# C64-usb-loader.net
KiCad netlist of a schematic drawn in EAGLE
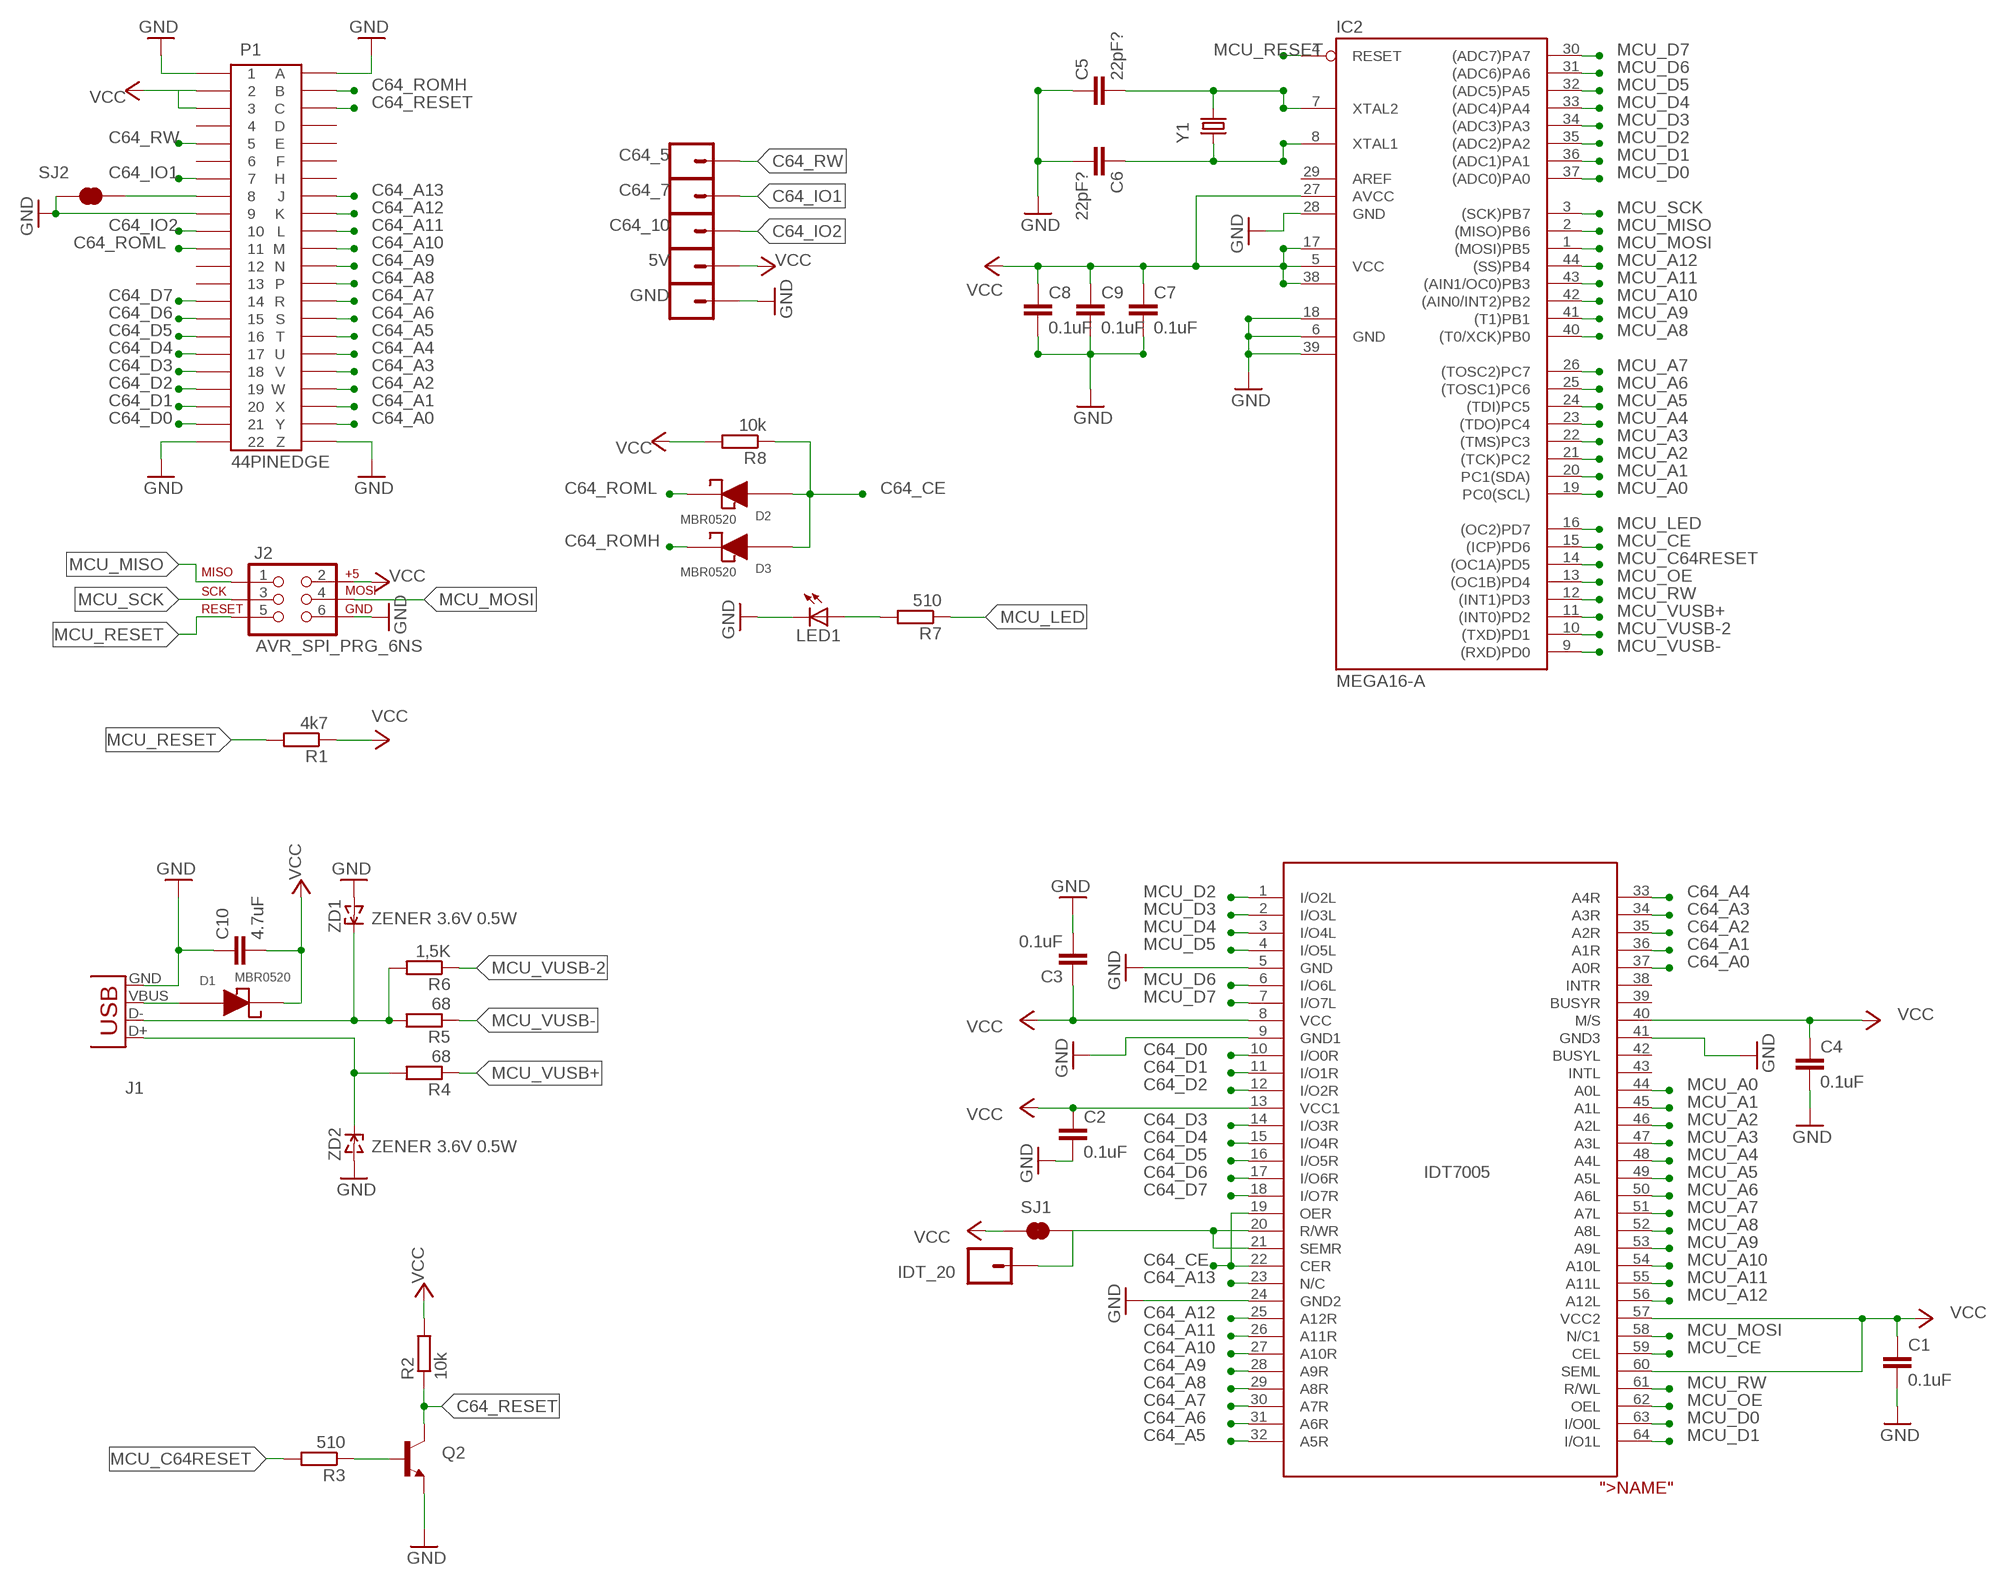
[diagram p0: schematic, sheet 1]

(export (version "E")
  (design (tool "Eeschema 10.0.6"))
  (components
    (comp (ref "5V")
      (value "M01PTH")
      (footprint "eagle-import:1X01")
      (libsource (lib "eagle-import") (part "M01PTH"))
    )
    (comp (ref "C1")
      (value "0.1uF")
      (footprint "eagle-import:C0805")
      (libsource (lib "eagle-import") (part "C-EUC0805"))
    )
    (comp (ref "C2")
      (value "0.1uF")
      (footprint "eagle-import:C0805")
      (libsource (lib "eagle-import") (part "C-EUC0805"))
    )
    (comp (ref "C3")
      (value "0.1uF")
      (footprint "eagle-import:C0805")
      (libsource (lib "eagle-import") (part "C-EUC0805"))
    )
    (comp (ref "C4")
      (value "0.1uF")
      (footprint "eagle-import:C0805")
      (libsource (lib "eagle-import") (part "C-EUC0805"))
    )
    (comp (ref "C5")
      (value "22pF?")
      (footprint "eagle-import:C0805")
      (libsource (lib "eagle-import") (part "C-EUC0805"))
    )
    (comp (ref "C6")
      (value "22pF?")
      (footprint "eagle-import:C0805")
      (libsource (lib "eagle-import") (part "C-EUC0805"))
    )
    (comp (ref "C7")
      (value "0.1uF")
      (footprint "eagle-import:C0805")
      (libsource (lib "eagle-import") (part "C-EUC0805"))
    )
    (comp (ref "C8")
      (value "0.1uF")
      (footprint "eagle-import:C0805")
      (libsource (lib "eagle-import") (part "C-EUC0805"))
    )
    (comp (ref "C9")
      (value "0.1uF")
      (footprint "eagle-import:C0805")
      (libsource (lib "eagle-import") (part "C-EUC0805"))
    )
    (comp (ref "C10")
      (value "4.7uF")
      (footprint "eagle-import:C0805")
      (libsource (lib "eagle-import") (part "C-EUC0805"))
    )
    (comp (ref "C64_5")
      (value "M01PTH")
      (footprint "eagle-import:1X01")
      (libsource (lib "eagle-import") (part "M01PTH"))
    )
    (comp (ref "C64_7")
      (value "M01PTH")
      (footprint "eagle-import:1X01")
      (libsource (lib "eagle-import") (part "M01PTH"))
    )
    (comp (ref "C64_10")
      (value "M01PTH")
      (footprint "eagle-import:1X01")
      (libsource (lib "eagle-import") (part "M01PTH"))
    )
    (comp (ref "D1")
      (value "MBR0520")
      (footprint "eagle-import:SOD-123")
      (libsource (lib "eagle-import") (part "MBR0520"))
    )
    (comp (ref "D2")
      (value "MBR0520")
      (footprint "eagle-import:SOD-123")
      (libsource (lib "eagle-import") (part "MBR0520"))
    )
    (comp (ref "D3")
      (value "MBR0520")
      (footprint "eagle-import:SOD-123")
      (libsource (lib "eagle-import") (part "MBR0520"))
    )
    (comp (ref "GND")
      (value "M01PTH")
      (footprint "eagle-import:1X01")
      (libsource (lib "eagle-import") (part "M01PTH"))
    )
    (comp (ref "IC1")
      (value "IDT7005")
      (footprint "eagle-import:TQFP64")
      (libsource (lib "eagle-import") (part "IDT7005"))
    )
    (comp (ref "IC2")
      (value "MEGA16-A")
      (footprint "eagle-import:TQFP44")
      (fields (field (name "MPN") "ATMEGA16-16AU"))
      (libsource (lib "eagle-import") (part "MEGA16-A"))
    )
    (comp (ref "IDT_20")
      (value "M01PTH")
      (footprint "eagle-import:1X01")
      (libsource (lib "eagle-import") (part "M01PTH"))
    )
    (comp (ref "J1")
      (value "USB-B")
      (footprint "eagle-import:B")
      (libsource (lib "eagle-import") (part "USB-B"))
    )
    (comp (ref "J2")
      (value "AVR_SPI_PRG_6NS")
      (footprint "eagle-import:2X3-NS")
      (libsource (lib "eagle-import") (part "AVR_SPI_PRG_6NS"))
    )
    (comp (ref "LED1")
      (value "LED1206")
      (footprint "eagle-import:LED-1206")
      (libsource (lib "eagle-import") (part "LED1206"))
    )
    (comp (ref "P1")
      (value "44PINEDGE")
      (footprint "eagle-import:44PINEDGE")
      (libsource (lib "eagle-import") (part "44PINEDGE"))
    )
    (comp (ref "Q2")
      (value "TRANSISTOR_NPNSOT23-3")
      (footprint "eagle-import:SOT23-3")
      (libsource (lib "eagle-import") (part "TRANSISTOR_NPNSOT23-3"))
    )
    (comp (ref "R1")
      (value "4k7")
      (footprint "eagle-import:M0805")
      (libsource (lib "eagle-import") (part "R-EU_M0805"))
    )
    (comp (ref "R2")
      (value "10k")
      (footprint "eagle-import:M0805")
      (libsource (lib "eagle-import") (part "R-EU_M0805"))
    )
    (comp (ref "R3")
      (value "510")
      (footprint "eagle-import:M0805")
      (libsource (lib "eagle-import") (part "R-EU_M0805"))
    )
    (comp (ref "R4")
      (value "68")
      (footprint "eagle-import:M0805")
      (libsource (lib "eagle-import") (part "R-EU_M0805"))
    )
    (comp (ref "R5")
      (value "68")
      (footprint "eagle-import:M0805")
      (libsource (lib "eagle-import") (part "R-EU_M0805"))
    )
    (comp (ref "R6")
      (value "1,5K")
      (footprint "eagle-import:M0805")
      (libsource (lib "eagle-import") (part "R-EU_M0805"))
    )
    (comp (ref "R7")
      (value "510")
      (footprint "eagle-import:M0805")
      (libsource (lib "eagle-import") (part "R-EU_M0805"))
    )
    (comp (ref "R8")
      (value "10k")
      (footprint "eagle-import:M0805")
      (libsource (lib "eagle-import") (part "R-EU_M0805"))
    )
    (comp (ref "SJ1")
      (value "JUMPER-PAD-2-NC_BY_TRACE")
      (footprint "eagle-import:PAD-JUMPER-2-NC_BY_TRACE_YES_SILK")
      (libsource (lib "eagle-import") (part "JUMPER-PAD-2-NC_BY_TRACE"))
    )
    (comp (ref "SJ2")
      (value "JUMPER-PAD-2-NC_BY_TRACE")
      (footprint "eagle-import:PAD-JUMPER-2-NC_BY_TRACE_YES_SILK")
      (libsource (lib "eagle-import") (part "JUMPER-PAD-2-NC_BY_TRACE"))
    )
    (comp (ref "Y1")
      (value "CRYSTALHC49US")
      (footprint "eagle-import:HC49US")
      (libsource (lib "eagle-import") (part "CRYSTALHC49US"))
    )
    (comp (ref "ZD1")
      (value "ZENER 3.6V 0.5W")
      (footprint "eagle-import:SOD-123")
      (libsource (lib "eagle-import") (part "ZENERSOD-123"))
    )
    (comp (ref "ZD2")
      (value "ZENER 3.6V 0.5W")
      (footprint "eagle-import:SOD-123")
      (libsource (lib "eagle-import") (part "ZENERSOD-123"))
    )
  )
  (nets
    (net (code "1") (name "/C64_A0") (class "Default")
      (node (ref "IC1") (pin "37") (pinfunction "A0R_37") (pintype "bidirectional"))
      (node (ref "P1") (pin "Y") (pinfunction "Y_Y") (pintype "passive"))
    )
    (net (code "2") (name "/C64_A1") (class "Default")
      (node (ref "IC1") (pin "36") (pinfunction "A1R_36") (pintype "bidirectional"))
      (node (ref "P1") (pin "X") (pinfunction "X_X") (pintype "passive"))
    )
    (net (code "3") (name "/C64_A2") (class "Default")
      (node (ref "IC1") (pin "35") (pinfunction "A2R_35") (pintype "bidirectional"))
      (node (ref "P1") (pin "W") (pinfunction "W_W") (pintype "passive"))
    )
    (net (code "4") (name "/C64_A3") (class "Default")
      (node (ref "IC1") (pin "34") (pinfunction "A3R_34") (pintype "bidirectional"))
      (node (ref "P1") (pin "V") (pinfunction "V_V") (pintype "passive"))
    )
    (net (code "5") (name "/C64_A4") (class "Default")
      (node (ref "IC1") (pin "33") (pinfunction "A4R_33") (pintype "bidirectional"))
      (node (ref "P1") (pin "U") (pinfunction "U_U") (pintype "passive"))
    )
    (net (code "6") (name "/C64_A5") (class "Default")
      (node (ref "IC1") (pin "32") (pinfunction "A5R_32") (pintype "bidirectional"))
      (node (ref "P1") (pin "T") (pinfunction "T_T") (pintype "passive"))
    )
    (net (code "7") (name "/C64_A6") (class "Default")
      (node (ref "IC1") (pin "31") (pinfunction "A6R_31") (pintype "bidirectional"))
      (node (ref "P1") (pin "S") (pinfunction "S_S") (pintype "passive"))
    )
    (net (code "8") (name "/C64_A7") (class "Default")
      (node (ref "IC1") (pin "30") (pinfunction "A7R_30") (pintype "bidirectional"))
      (node (ref "P1") (pin "R") (pinfunction "R_R") (pintype "passive"))
    )
    (net (code "9") (name "/C64_A8") (class "Default")
      (node (ref "IC1") (pin "29") (pinfunction "A8R_29") (pintype "bidirectional"))
      (node (ref "P1") (pin "P") (pinfunction "P_P") (pintype "passive"))
    )
    (net (code "10") (name "/C64_A9") (class "Default")
      (node (ref "IC1") (pin "28") (pinfunction "A9R_28") (pintype "bidirectional"))
      (node (ref "P1") (pin "N") (pinfunction "N_N") (pintype "passive"))
    )
    (net (code "11") (name "/C64_A10") (class "Default")
      (node (ref "IC1") (pin "27") (pinfunction "A10R_27") (pintype "bidirectional"))
      (node (ref "P1") (pin "M") (pinfunction "M_M") (pintype "passive"))
    )
    (net (code "12") (name "/C64_A11") (class "Default")
      (node (ref "IC1") (pin "26") (pinfunction "A11R_26") (pintype "bidirectional"))
      (node (ref "P1") (pin "L") (pinfunction "L_L") (pintype "passive"))
    )
    (net (code "13") (name "/C64_A12") (class "Default")
      (node (ref "IC1") (pin "25") (pinfunction "A12R_25") (pintype "bidirectional"))
      (node (ref "P1") (pin "K") (pinfunction "K_K") (pintype "passive"))
    )
    (net (code "14") (name "/C64_A13") (class "Default")
      (node (ref "IC1") (pin "23") (pinfunction "N/C_23") (pintype "bidirectional"))
      (node (ref "P1") (pin "J") (pinfunction "J_J") (pintype "passive"))
    )
    (net (code "15") (name "/C64_CE") (class "Default")
      (node (ref "D2") (pin "2") (pinfunction "AN_2") (pintype "passive"))
      (node (ref "D3") (pin "2") (pinfunction "AN_2") (pintype "passive"))
      (node (ref "IC1") (pin "19") (pinfunction "OER_19") (pintype "bidirectional"))
      (node (ref "IC1") (pin "22") (pinfunction "CER_22") (pintype "bidirectional"))
      (node (ref "R8") (pin "1") (pinfunction "1_1") (pintype "passive"))
    )
    (net (code "16") (name "/C64_D0") (class "Default")
      (node (ref "IC1") (pin "10") (pinfunction "I/O0R_10") (pintype "bidirectional"))
      (node (ref "P1") (pin "21") (pinfunction "21_21") (pintype "passive"))
    )
    (net (code "17") (name "/C64_D1") (class "Default")
      (node (ref "IC1") (pin "11") (pinfunction "I/O1R_11") (pintype "bidirectional"))
      (node (ref "P1") (pin "20") (pinfunction "20_20") (pintype "passive"))
    )
    (net (code "18") (name "/C64_D2") (class "Default")
      (node (ref "IC1") (pin "12") (pinfunction "I/O2R_12") (pintype "bidirectional"))
      (node (ref "P1") (pin "19") (pinfunction "19_19") (pintype "passive"))
    )
    (net (code "19") (name "/C64_D3") (class "Default")
      (node (ref "IC1") (pin "14") (pinfunction "I/O3R_14") (pintype "bidirectional"))
      (node (ref "P1") (pin "18") (pinfunction "18_18") (pintype "passive"))
    )
    (net (code "20") (name "/C64_D4") (class "Default")
      (node (ref "IC1") (pin "15") (pinfunction "I/O4R_15") (pintype "bidirectional"))
      (node (ref "P1") (pin "17") (pinfunction "17_17") (pintype "passive"))
    )
    (net (code "21") (name "/C64_D5") (class "Default")
      (node (ref "IC1") (pin "16") (pinfunction "I/O5R_16") (pintype "bidirectional"))
      (node (ref "P1") (pin "16") (pinfunction "16_16") (pintype "passive"))
    )
    (net (code "22") (name "/C64_D6") (class "Default")
      (node (ref "IC1") (pin "17") (pinfunction "I/O6R_17") (pintype "bidirectional"))
      (node (ref "P1") (pin "15") (pinfunction "15_15") (pintype "passive"))
    )
    (net (code "23") (name "/C64_D7") (class "Default")
      (node (ref "IC1") (pin "18") (pinfunction "I/O7R_18") (pintype "bidirectional"))
      (node (ref "P1") (pin "14") (pinfunction "14_14") (pintype "passive"))
    )
    (net (code "24") (name "/C64_ROMH") (class "Default")
      (node (ref "D3") (pin "1") (pinfunction "CA_1") (pintype "passive"))
      (node (ref "P1") (pin "B") (pinfunction "B_B") (pintype "passive"))
    )
    (net (code "25") (name "/C64_ROML") (class "Default")
      (node (ref "D2") (pin "1") (pinfunction "CA_1") (pintype "passive"))
      (node (ref "P1") (pin "11") (pinfunction "11_11") (pintype "passive"))
    )
    (net (code "26") (name "/MCU_A0") (class "Default")
      (node (ref "IC1") (pin "44") (pinfunction "A0L_44") (pintype "bidirectional"))
      (node (ref "IC2") (pin "19") (pinfunction "PC0(SCL)_19") (pintype "bidirectional"))
    )
    (net (code "27") (name "/MCU_A1") (class "Default")
      (node (ref "IC1") (pin "45") (pinfunction "A1L_45") (pintype "bidirectional"))
      (node (ref "IC2") (pin "20") (pinfunction "PC1(SDA)_20") (pintype "bidirectional"))
    )
    (net (code "28") (name "/MCU_A2") (class "Default")
      (node (ref "IC1") (pin "46") (pinfunction "A2L_46") (pintype "bidirectional"))
      (node (ref "IC2") (pin "21") (pinfunction "(TCK)PC2_21") (pintype "bidirectional"))
    )
    (net (code "29") (name "/MCU_A3") (class "Default")
      (node (ref "IC1") (pin "47") (pinfunction "A3L_47") (pintype "bidirectional"))
      (node (ref "IC2") (pin "22") (pinfunction "(TMS)PC3_22") (pintype "bidirectional"))
    )
    (net (code "30") (name "/MCU_A4") (class "Default")
      (node (ref "IC1") (pin "48") (pinfunction "A4L_48") (pintype "bidirectional"))
      (node (ref "IC2") (pin "23") (pinfunction "(TDO)PC4_23") (pintype "bidirectional"))
    )
    (net (code "31") (name "/MCU_A5") (class "Default")
      (node (ref "IC1") (pin "49") (pinfunction "A5L_49") (pintype "bidirectional"))
      (node (ref "IC2") (pin "24") (pinfunction "(TDI)PC5_24") (pintype "bidirectional"))
    )
    (net (code "32") (name "/MCU_A6") (class "Default")
      (node (ref "IC1") (pin "50") (pinfunction "A6L_50") (pintype "bidirectional"))
      (node (ref "IC2") (pin "25") (pinfunction "(TOSC1)PC6_25") (pintype "bidirectional"))
    )
    (net (code "33") (name "/MCU_A7") (class "Default")
      (node (ref "IC1") (pin "51") (pinfunction "A7L_51") (pintype "bidirectional"))
      (node (ref "IC2") (pin "26") (pinfunction "(TOSC2)PC7_26") (pintype "bidirectional"))
    )
    (net (code "34") (name "/MCU_A8") (class "Default")
      (node (ref "IC1") (pin "52") (pinfunction "A8L_52") (pintype "bidirectional"))
      (node (ref "IC2") (pin "40") (pinfunction "(T0/XCK)PB0_40") (pintype "bidirectional"))
    )
    (net (code "35") (name "/MCU_A9") (class "Default")
      (node (ref "IC1") (pin "53") (pinfunction "A9L_53") (pintype "bidirectional"))
      (node (ref "IC2") (pin "41") (pinfunction "(T1)PB1_41") (pintype "bidirectional"))
    )
    (net (code "36") (name "/MCU_A10") (class "Default")
      (node (ref "IC1") (pin "54") (pinfunction "A10L_54") (pintype "bidirectional"))
      (node (ref "IC2") (pin "42") (pinfunction "(AIN0/INT2)PB2_42") (pintype "bidirectional"))
    )
    (net (code "37") (name "/MCU_A11") (class "Default")
      (node (ref "IC1") (pin "55") (pinfunction "A11L_55") (pintype "bidirectional"))
      (node (ref "IC2") (pin "43") (pinfunction "(AIN1/OC0)PB3_43") (pintype "bidirectional"))
    )
    (net (code "38") (name "/MCU_A12") (class "Default")
      (node (ref "IC1") (pin "56") (pinfunction "A12L_56") (pintype "bidirectional"))
      (node (ref "IC2") (pin "44") (pinfunction "(SS)PB4_44") (pintype "bidirectional"))
    )
    (net (code "39") (name "/MCU_CE") (class "Default")
      (node (ref "IC1") (pin "59") (pinfunction "CEL_59") (pintype "bidirectional"))
      (node (ref "IC2") (pin "15") (pinfunction "(ICP)PD6_15") (pintype "bidirectional"))
    )
    (net (code "40") (name "/MCU_D0") (class "Default")
      (node (ref "IC1") (pin "63") (pinfunction "I/O0L_63") (pintype "bidirectional"))
      (node (ref "IC2") (pin "37") (pinfunction "(ADC0)PA0_37") (pintype "bidirectional"))
    )
    (net (code "41") (name "/MCU_D1") (class "Default")
      (node (ref "IC1") (pin "64") (pinfunction "I/O1L_64") (pintype "bidirectional"))
      (node (ref "IC2") (pin "36") (pinfunction "(ADC1)PA1_36") (pintype "bidirectional"))
    )
    (net (code "42") (name "/MCU_D2") (class "Default")
      (node (ref "IC1") (pin "1") (pinfunction "I/O2L_1") (pintype "bidirectional"))
      (node (ref "IC2") (pin "35") (pinfunction "(ADC2)PA2_35") (pintype "bidirectional"))
    )
    (net (code "43") (name "/MCU_D3") (class "Default")
      (node (ref "IC1") (pin "2") (pinfunction "I/O3L_2") (pintype "bidirectional"))
      (node (ref "IC2") (pin "34") (pinfunction "(ADC3)PA3_34") (pintype "bidirectional"))
    )
    (net (code "44") (name "/MCU_D4") (class "Default")
      (node (ref "IC1") (pin "3") (pinfunction "I/O4L_3") (pintype "bidirectional"))
      (node (ref "IC2") (pin "33") (pinfunction "(ADC4)PA4_33") (pintype "bidirectional"))
    )
    (net (code "45") (name "/MCU_D5") (class "Default")
      (node (ref "IC1") (pin "4") (pinfunction "I/O5L_4") (pintype "bidirectional"))
      (node (ref "IC2") (pin "32") (pinfunction "(ADC5)PA5_32") (pintype "bidirectional"))
    )
    (net (code "46") (name "/MCU_D6") (class "Default")
      (node (ref "IC1") (pin "6") (pinfunction "I/O6L_6") (pintype "bidirectional"))
      (node (ref "IC2") (pin "31") (pinfunction "(ADC6)PA6_31") (pintype "bidirectional"))
    )
    (net (code "47") (name "/MCU_D7") (class "Default")
      (node (ref "IC1") (pin "7") (pinfunction "I/O7L_7") (pintype "bidirectional"))
      (node (ref "IC2") (pin "30") (pinfunction "(ADC7)PA7_30") (pintype "bidirectional"))
    )
    (net (code "48") (name "/MCU_OE") (class "Default")
      (node (ref "IC1") (pin "62") (pinfunction "OEL_62") (pintype "bidirectional"))
      (node (ref "IC2") (pin "13") (pinfunction "(OC1B)PD4_13") (pintype "bidirectional"))
    )
    (net (code "49") (name "/MCU_RW") (class "Default")
      (node (ref "IC1") (pin "61") (pinfunction "R/WL_61") (pintype "bidirectional"))
      (node (ref "IC2") (pin "12") (pinfunction "(INT1)PD3_12") (pintype "bidirectional"))
    )
    (net (code "50") (name "C64_IO1") (class "Default")
      (node (ref "C64_7") (pin "1") (pinfunction "1_1") (pintype "passive"))
      (node (ref "P1") (pin "7") (pinfunction "7_7") (pintype "passive"))
    )
    (net (code "51") (name "C64_IO2") (class "Default")
      (node (ref "C64_10") (pin "1") (pinfunction "1_1") (pintype "passive"))
      (node (ref "P1") (pin "10") (pinfunction "10_10") (pintype "passive"))
    )
    (net (code "52") (name "C64_RESET") (class "Default")
      (node (ref "P1") (pin "C") (pinfunction "C_C") (pintype "passive"))
      (node (ref "Q2") (pin "3") (pinfunction "C_3") (pintype "passive"))
      (node (ref "R2") (pin "1") (pinfunction "1_1") (pintype "passive"))
    )
    (net (code "53") (name "C64_RW") (class "Default")
      (node (ref "C64_5") (pin "1") (pinfunction "1_1") (pintype "passive"))
      (node (ref "P1") (pin "5") (pinfunction "5_5") (pintype "passive"))
    )
    (net (code "54") (name "GND") (class "Default")
      (node (ref "C1") (pin "2") (pinfunction "2_2") (pintype "passive"))
      (node (ref "C10") (pin "1") (pinfunction "1_1") (pintype "passive"))
      (node (ref "C2") (pin "2") (pinfunction "2_2") (pintype "passive"))
      (node (ref "C3") (pin "2") (pinfunction "2_2") (pintype "passive"))
      (node (ref "C4") (pin "2") (pinfunction "2_2") (pintype "passive"))
      (node (ref "C5") (pin "1") (pinfunction "1_1") (pintype "passive"))
      (node (ref "C6") (pin "2") (pinfunction "2_2") (pintype "passive"))
      (node (ref "C7") (pin "2") (pinfunction "2_2") (pintype "passive"))
      (node (ref "C8") (pin "2") (pinfunction "2_2") (pintype "passive"))
      (node (ref "C9") (pin "2") (pinfunction "2_2") (pintype "passive"))
      (node (ref "GND") (pin "1") (pinfunction "1_1") (pintype "passive"))
      (node (ref "IC1") (pin "24") (pinfunction "GND2_24") (pintype "bidirectional"))
      (node (ref "IC1") (pin "41") (pinfunction "GND3_41") (pintype "bidirectional"))
      (node (ref "IC1") (pin "5") (pinfunction "GND_5") (pintype "bidirectional"))
      (node (ref "IC1") (pin "9") (pinfunction "GND1_9") (pintype "bidirectional"))
      (node (ref "IC2") (pin "18") (pinfunction "GND1_18") (pintype "power_in"))
      (node (ref "IC2") (pin "28") (pinfunction "GND_28") (pintype "power_in"))
      (node (ref "IC2") (pin "39") (pinfunction "GND2_39") (pintype "power_in"))
      (node (ref "IC2") (pin "6") (pinfunction "GND_6") (pintype "power_in"))
      (node (ref "J1") (pin "GND") (pinfunction "GND_GND") (pintype "bidirectional"))
      (node (ref "J2") (pin "6") (pinfunction "6_6") (pintype "passive"))
      (node (ref "LED1") (pin "C") (pinfunction "C_C") (pintype "passive"))
      (node (ref "P1") (pin "1") (pinfunction "1_1") (pintype "passive"))
      (node (ref "P1") (pin "22") (pinfunction "22_22") (pintype "passive"))
      (node (ref "P1") (pin "9") (pinfunction "9_9") (pintype "passive"))
      (node (ref "P1") (pin "A") (pinfunction "A_A") (pintype "passive"))
      (node (ref "P1") (pin "Z") (pinfunction "Z_Z") (pintype "passive"))
      (node (ref "Q2") (pin "2") (pinfunction "E_2") (pintype "passive"))
      (node (ref "SJ2") (pin "1") (pinfunction "1_1") (pintype "passive"))
      (node (ref "ZD1") (pin "A") (pinfunction "A_A") (pintype "passive"))
      (node (ref "ZD2") (pin "A") (pinfunction "A_A") (pintype "passive"))
    )
    (net (code "55") (name "MCU_C64RESET") (class "Default")
      (node (ref "IC2") (pin "14") (pinfunction "(OC1A)PD5_14") (pintype "bidirectional"))
      (node (ref "R3") (pin "2") (pinfunction "2_2") (pintype "passive"))
    )
    (net (code "56") (name "MCU_LED") (class "Default")
      (node (ref "IC2") (pin "16") (pinfunction "(OC2)PD7_16") (pintype "bidirectional"))
      (node (ref "R7") (pin "1") (pinfunction "1_1") (pintype "passive"))
    )
    (net (code "57") (name "MCU_MISO") (class "Default")
      (node (ref "IC2") (pin "2") (pinfunction "(MISO)PB6_2") (pintype "bidirectional"))
      (node (ref "J2") (pin "1") (pinfunction "1_1") (pintype "passive"))
    )
    (net (code "58") (name "MCU_MOSI") (class "Default")
      (node (ref "IC1") (pin "58") (pinfunction "N/C1_58") (pintype "bidirectional"))
      (node (ref "IC2") (pin "1") (pinfunction "(MOSI)PB5_1") (pintype "bidirectional"))
      (node (ref "J2") (pin "4") (pinfunction "4_4") (pintype "passive"))
    )
    (net (code "59") (name "MCU_RESET") (class "Default")
      (node (ref "IC2") (pin "4") (pinfunction "RESET_4") (pintype "input"))
      (node (ref "J2") (pin "5") (pinfunction "5_5") (pintype "passive"))
      (node (ref "R1") (pin "2") (pinfunction "2_2") (pintype "passive"))
    )
    (net (code "60") (name "MCU_SCK") (class "Default")
      (node (ref "IC2") (pin "3") (pinfunction "(SCK)PB7_3") (pintype "bidirectional"))
      (node (ref "J2") (pin "3") (pinfunction "3_3") (pintype "passive"))
    )
    (net (code "61") (name "MCU_VUSB+") (class "Default")
      (node (ref "IC2") (pin "11") (pinfunction "(INT0)PD2_11") (pintype "bidirectional"))
      (node (ref "R4") (pin "1") (pinfunction "1_1") (pintype "passive"))
    )
    (net (code "62") (name "MCU_VUSB-") (class "Default")
      (node (ref "IC2") (pin "9") (pinfunction "(RXD)PD0_9") (pintype "bidirectional"))
      (node (ref "R5") (pin "1") (pinfunction "1_1") (pintype "passive"))
    )
    (net (code "63") (name "MCU_VUSB-2") (class "Default")
      (node (ref "IC2") (pin "10") (pinfunction "(TXD)PD1_10") (pintype "bidirectional"))
      (node (ref "R6") (pin "1") (pinfunction "1_1") (pintype "passive"))
    )
    (net (code "64") (name "Net-(D1-AN)") (class "Default")
      (node (ref "D1") (pin "2") (pinfunction "AN_2") (pintype "passive"))
      (node (ref "J1") (pin "VBUS") (pinfunction "VBUS_VBUS") (pintype "bidirectional"))
    )
    (net (code "65") (name "Net-(IC1-R{slash}WR)") (class "Default")
      (node (ref "IC1") (pin "20") (pinfunction "R/WR_20") (pintype "bidirectional"))
      (node (ref "IC1") (pin "21") (pinfunction "SEMR_21") (pintype "bidirectional"))
      (node (ref "IDT_20") (pin "1") (pinfunction "1_1") (pintype "passive"))
      (node (ref "SJ1") (pin "2") (pinfunction "2_2") (pintype "passive"))
    )
    (net (code "66") (name "Net-(IC2-XTAL1)") (class "Default")
      (node (ref "C6") (pin "1") (pinfunction "1_1") (pintype "passive"))
      (node (ref "IC2") (pin "8") (pinfunction "XTAL1_8") (pintype "bidirectional"))
      (node (ref "Y1") (pin "1") (pinfunction "1_1") (pintype "passive"))
    )
    (net (code "67") (name "Net-(IC2-XTAL2)") (class "Default")
      (node (ref "C5") (pin "2") (pinfunction "2_2") (pintype "passive"))
      (node (ref "IC2") (pin "7") (pinfunction "XTAL2_7") (pintype "bidirectional"))
      (node (ref "Y1") (pin "2") (pinfunction "2_2") (pintype "passive"))
    )
    (net (code "68") (name "Net-(J1-PadD+)") (class "Default")
      (node (ref "J1") (pin "D+") (pinfunction "D+_D+") (pintype "bidirectional"))
      (node (ref "R4") (pin "2") (pinfunction "2_2") (pintype "passive"))
      (node (ref "ZD2") (pin "C") (pinfunction "C_C") (pintype "passive"))
    )
    (net (code "69") (name "Net-(J1-PadD-)") (class "Default")
      (node (ref "J1") (pin "D-") (pinfunction "D-_D-") (pintype "bidirectional"))
      (node (ref "R5") (pin "2") (pinfunction "2_2") (pintype "passive"))
      (node (ref "R6") (pin "2") (pinfunction "2_2") (pintype "passive"))
      (node (ref "ZD1") (pin "C") (pinfunction "C_C") (pintype "passive"))
    )
    (net (code "70") (name "Net-(LED1-PadA)") (class "Default")
      (node (ref "LED1") (pin "A") (pinfunction "A_A") (pintype "passive"))
      (node (ref "R7") (pin "2") (pinfunction "2_2") (pintype "passive"))
    )
    (net (code "71") (name "Net-(P1-Pad8)") (class "Default")
      (node (ref "P1") (pin "8") (pinfunction "8_8") (pintype "passive"))
      (node (ref "SJ2") (pin "2") (pinfunction "2_2") (pintype "passive"))
    )
    (net (code "72") (name "Net-(Q2-B)") (class "Default")
      (node (ref "Q2") (pin "1") (pinfunction "B_1") (pintype "passive"))
      (node (ref "R3") (pin "1") (pinfunction "1_1") (pintype "passive"))
    )
    (net (code "73") (name "VCC") (class "Default")
      (node (ref "5V") (pin "1") (pinfunction "1_1") (pintype "passive"))
      (node (ref "C1") (pin "1") (pinfunction "1_1") (pintype "passive"))
      (node (ref "C10") (pin "2") (pinfunction "2_2") (pintype "passive"))
      (node (ref "C2") (pin "1") (pinfunction "1_1") (pintype "passive"))
      (node (ref "C3") (pin "1") (pinfunction "1_1") (pintype "passive"))
      (node (ref "C4") (pin "1") (pinfunction "1_1") (pintype "passive"))
      (node (ref "C7") (pin "1") (pinfunction "1_1") (pintype "passive"))
      (node (ref "C8") (pin "1") (pinfunction "1_1") (pintype "passive"))
      (node (ref "C9") (pin "1") (pinfunction "1_1") (pintype "passive"))
      (node (ref "D1") (pin "1") (pinfunction "CA_1") (pintype "passive"))
      (node (ref "IC1") (pin "13") (pinfunction "VCC1_13") (pintype "bidirectional"))
      (node (ref "IC1") (pin "40") (pinfunction "M/S_40") (pintype "bidirectional"))
      (node (ref "IC1") (pin "57") (pinfunction "VCC2_57") (pintype "bidirectional"))
      (node (ref "IC1") (pin "60") (pinfunction "SEML_60") (pintype "bidirectional"))
      (node (ref "IC1") (pin "8") (pinfunction "VCC_8") (pintype "bidirectional"))
      (node (ref "IC2") (pin "17") (pinfunction "VCC1_17") (pintype "power_in"))
      (node (ref "IC2") (pin "27") (pinfunction "AVCC_27") (pintype "power_in"))
      (node (ref "IC2") (pin "38") (pinfunction "VCC2_38") (pintype "power_in"))
      (node (ref "IC2") (pin "5") (pinfunction "VCC_5") (pintype "power_in"))
      (node (ref "J2") (pin "2") (pinfunction "2_2") (pintype "passive"))
      (node (ref "P1") (pin "2") (pinfunction "2_2") (pintype "passive"))
      (node (ref "P1") (pin "3") (pinfunction "3_3") (pintype "passive"))
      (node (ref "R1") (pin "1") (pinfunction "1_1") (pintype "passive"))
      (node (ref "R2") (pin "2") (pinfunction "2_2") (pintype "passive"))
      (node (ref "R8") (pin "2") (pinfunction "2_2") (pintype "passive"))
      (node (ref "SJ1") (pin "1") (pinfunction "1_1") (pintype "passive"))
    )
    (net (code "74") (name "unconnected-(IC1-BUSYL-Pad42)") (class "Default")
      (node (ref "IC1") (pin "42") (pinfunction "BUSYL_42") (pintype "bidirectional"))
    )
    (net (code "75") (name "unconnected-(IC1-BUSYR-Pad39)") (class "Default")
      (node (ref "IC1") (pin "39") (pinfunction "BUSYR_39") (pintype "bidirectional"))
    )
    (net (code "76") (name "unconnected-(IC1-INTL-Pad43)") (class "Default")
      (node (ref "IC1") (pin "43") (pinfunction "INTL_43") (pintype "bidirectional"))
    )
    (net (code "77") (name "unconnected-(IC1-INTR-Pad38)") (class "Default")
      (node (ref "IC1") (pin "38") (pinfunction "INTR_38") (pintype "bidirectional"))
    )
    (net (code "78") (name "unconnected-(IC2-AREF-Pad29)") (class "Default")
      (node (ref "IC2") (pin "29") (pinfunction "AREF_29") (pintype "passive"))
    )
    (net (code "79") (name "unconnected-(P1-Pad4)") (class "Default")
      (node (ref "P1") (pin "4") (pinfunction "4_4") (pintype "passive"))
    )
    (net (code "80") (name "unconnected-(P1-Pad6)") (class "Default")
      (node (ref "P1") (pin "6") (pinfunction "6_6") (pintype "passive"))
    )
    (net (code "81") (name "unconnected-(P1-Pad12)") (class "Default")
      (node (ref "P1") (pin "12") (pinfunction "12_12") (pintype "passive"))
    )
    (net (code "82") (name "unconnected-(P1-Pad13)") (class "Default")
      (node (ref "P1") (pin "13") (pinfunction "13_13") (pintype "passive"))
    )
    (net (code "83") (name "unconnected-(P1-PadD)") (class "Default")
      (node (ref "P1") (pin "D") (pinfunction "D_D") (pintype "passive"))
    )
    (net (code "84") (name "unconnected-(P1-PadE)") (class "Default")
      (node (ref "P1") (pin "E") (pinfunction "E_E") (pintype "passive"))
    )
    (net (code "85") (name "unconnected-(P1-PadF)") (class "Default")
      (node (ref "P1") (pin "F") (pinfunction "F_F") (pintype "passive"))
    )
    (net (code "86") (name "unconnected-(P1-PadH)") (class "Default")
      (node (ref "P1") (pin "H") (pinfunction "H_H") (pintype "passive"))
    )
  )
)
